# huskylens_servo.net
KiCad netlist of a schematic drawn in EAGLE
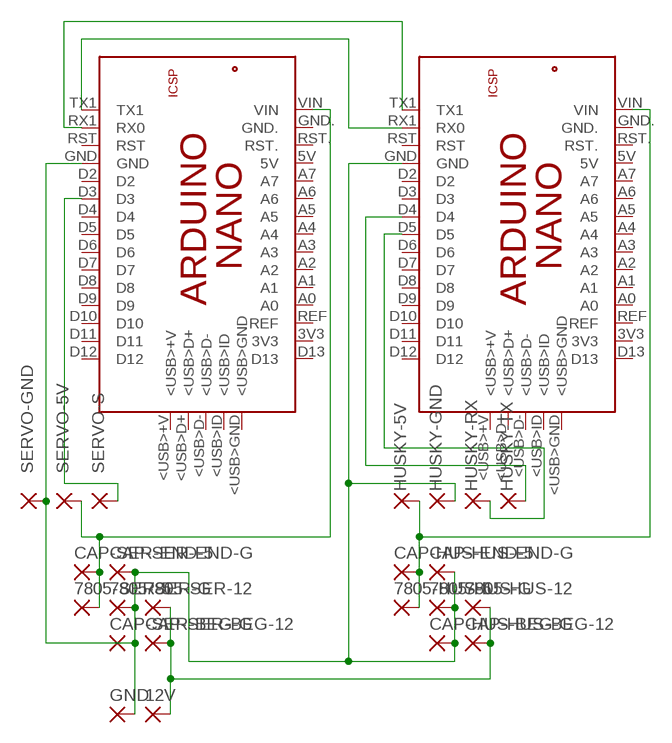
[diagram p0: schematic, sheet 1]

(export (version "E")
  (design (tool "Eeschema 10.0.6"))
  (components
    (comp (ref "12V")
      (value "2,15/1,0")
      (footprint "eagle-import:2,15_1,0")
      (libsource (lib "eagle-import") (part "2,15/1,0"))
    )
    (comp (ref "7805-HUS-5")
      (value "2,15/1,0")
      (footprint "eagle-import:2,15_1,0")
      (libsource (lib "eagle-import") (part "2,15/1,0"))
    )
    (comp (ref "7805-HUS-12")
      (value "2,15/1,0")
      (footprint "eagle-import:2,15_1,0")
      (libsource (lib "eagle-import") (part "2,15/1,0"))
    )
    (comp (ref "7805-HUS-G")
      (value "2,15/1,0")
      (footprint "eagle-import:2,15_1,0")
      (libsource (lib "eagle-import") (part "2,15/1,0"))
    )
    (comp (ref "7805-SER-5")
      (value "2,15/1,0")
      (footprint "eagle-import:2,15_1,0")
      (libsource (lib "eagle-import") (part "2,15/1,0"))
    )
    (comp (ref "7805-SER-12")
      (value "2,15/1,0")
      (footprint "eagle-import:2,15_1,0")
      (libsource (lib "eagle-import") (part "2,15/1,0"))
    )
    (comp (ref "7805-SER-G")
      (value "2,15/1,0")
      (footprint "eagle-import:2,15_1,0")
      (libsource (lib "eagle-import") (part "2,15/1,0"))
    )
    (comp (ref "CAP-HUS-BEG-12")
      (value "2,15/1,0")
      (footprint "eagle-import:2,15_1,0")
      (libsource (lib "eagle-import") (part "2,15/1,0"))
    )
    (comp (ref "CAP-HUS-BEG-G")
      (value "2,15/1,0")
      (footprint "eagle-import:2,15_1,0")
      (libsource (lib "eagle-import") (part "2,15/1,0"))
    )
    (comp (ref "CAP-HUS-END-5")
      (value "2,15/1,0")
      (footprint "eagle-import:2,15_1,0")
      (libsource (lib "eagle-import") (part "2,15/1,0"))
    )
    (comp (ref "CAP-HUS-END-G")
      (value "2,15/1,0")
      (footprint "eagle-import:2,15_1,0")
      (libsource (lib "eagle-import") (part "2,15/1,0"))
    )
    (comp (ref "CAP-SER-BEG-12")
      (value "2,15/1,0")
      (footprint "eagle-import:2,15_1,0")
      (libsource (lib "eagle-import") (part "2,15/1,0"))
    )
    (comp (ref "CAP-SER-BEG-G")
      (value "2,15/1,0")
      (footprint "eagle-import:2,15_1,0")
      (libsource (lib "eagle-import") (part "2,15/1,0"))
    )
    (comp (ref "CAP-SER-END-5")
      (value "2,15/1,0")
      (footprint "eagle-import:2,15_1,0")
      (libsource (lib "eagle-import") (part "2,15/1,0"))
    )
    (comp (ref "CAP-SER-END-G")
      (value "2,15/1,0")
      (footprint "eagle-import:2,15_1,0")
      (libsource (lib "eagle-import") (part "2,15/1,0"))
    )
    (comp (ref "GND")
      (value "2,15/1,0")
      (footprint "eagle-import:2,15_1,0")
      (libsource (lib "eagle-import") (part "2,15/1,0"))
    )
    (comp (ref "HUSKY-5V")
      (value "2,15/1,0")
      (footprint "eagle-import:2,15_1,0")
      (libsource (lib "eagle-import") (part "2,15/1,0"))
    )
    (comp (ref "HUSKY-ARD")
      (value "ARDUINO_NANO")
      (footprint "eagle-import:ARDUINO_NANO")
      (libsource (lib "eagle-import") (part "ARDUINO_NANO"))
    )
    (comp (ref "HUSKY-GND")
      (value "2,15/1,0")
      (footprint "eagle-import:2,15_1,0")
      (libsource (lib "eagle-import") (part "2,15/1,0"))
    )
    (comp (ref "HUSKY-RX")
      (value "2,15/1,0")
      (footprint "eagle-import:2,15_1,0")
      (libsource (lib "eagle-import") (part "2,15/1,0"))
    )
    (comp (ref "HUSKY-TX")
      (value "2,15/1,0")
      (footprint "eagle-import:2,15_1,0")
      (libsource (lib "eagle-import") (part "2,15/1,0"))
    )
    (comp (ref "SERVO-5V")
      (value "2,15/1,0")
      (footprint "eagle-import:2,15_1,0")
      (libsource (lib "eagle-import") (part "2,15/1,0"))
    )
    (comp (ref "SERVO-ARD")
      (value "ARDUINO_NANO")
      (footprint "eagle-import:ARDUINO_NANO")
      (libsource (lib "eagle-import") (part "ARDUINO_NANO"))
    )
    (comp (ref "SERVO-GND")
      (value "2,15/1,0")
      (footprint "eagle-import:2,15_1,0")
      (libsource (lib "eagle-import") (part "2,15/1,0"))
    )
    (comp (ref "SERVO-S")
      (value "2,15/1,0")
      (footprint "eagle-import:2,15_1,0")
      (libsource (lib "eagle-import") (part "2,15/1,0"))
    )
  )
  (nets
    (net (code "1") (name "Net-(12V-P)") (class "Default")
      (node (ref "12V") (pin "1") (pinfunction "P_1") (pintype "passive"))
      (node (ref "7805-HUS-12") (pin "1") (pinfunction "P_1") (pintype "passive"))
      (node (ref "7805-SER-12") (pin "1") (pinfunction "P_1") (pintype "passive"))
      (node (ref "CAP-HUS-BEG-12") (pin "1") (pinfunction "P_1") (pintype "passive"))
      (node (ref "CAP-SER-BEG-12") (pin "1") (pinfunction "P_1") (pintype "passive"))
    )
    (net (code "2") (name "Net-(7805-HUS-5-P)") (class "Default")
      (node (ref "7805-HUS-5") (pin "1") (pinfunction "P_1") (pintype "passive"))
      (node (ref "CAP-HUS-END-5") (pin "1") (pinfunction "P_1") (pintype "passive"))
      (node (ref "HUSKY-5V") (pin "1") (pinfunction "P_1") (pintype "passive"))
      (node (ref "HUSKY-ARD") (pin "VIN") (pinfunction "VIN_VIN") (pintype "bidirectional"))
    )
    (net (code "3") (name "Net-(7805-HUS-G-P)") (class "Default")
      (node (ref "7805-HUS-G") (pin "1") (pinfunction "P_1") (pintype "passive"))
      (node (ref "7805-SER-G") (pin "1") (pinfunction "P_1") (pintype "passive"))
      (node (ref "CAP-HUS-BEG-G") (pin "1") (pinfunction "P_1") (pintype "passive"))
      (node (ref "CAP-HUS-END-G") (pin "1") (pinfunction "P_1") (pintype "passive"))
      (node (ref "CAP-SER-BEG-G") (pin "1") (pinfunction "P_1") (pintype "passive"))
      (node (ref "CAP-SER-END-G") (pin "1") (pinfunction "P_1") (pintype "passive"))
      (node (ref "GND") (pin "1") (pinfunction "P_1") (pintype "passive"))
      (node (ref "HUSKY-ARD") (pin "GND") (pinfunction "GND_GND") (pintype "bidirectional"))
      (node (ref "HUSKY-GND") (pin "1") (pinfunction "P_1") (pintype "passive"))
      (node (ref "SERVO-ARD") (pin "GND") (pinfunction "GND_GND") (pintype "bidirectional"))
      (node (ref "SERVO-GND") (pin "1") (pinfunction "P_1") (pintype "passive"))
    )
    (net (code "4") (name "Net-(7805-SER-5-P)") (class "Default")
      (node (ref "7805-SER-5") (pin "1") (pinfunction "P_1") (pintype "passive"))
      (node (ref "CAP-SER-END-5") (pin "1") (pinfunction "P_1") (pintype "passive"))
      (node (ref "SERVO-5V") (pin "1") (pinfunction "P_1") (pintype "passive"))
      (node (ref "SERVO-ARD") (pin "VIN") (pinfunction "VIN_VIN") (pintype "bidirectional"))
    )
    (net (code "5") (name "Net-(HUSKY-ARD-RX0)") (class "Default")
      (node (ref "HUSKY-ARD") (pin "RX1") (pinfunction "RX0_RX1") (pintype "bidirectional"))
      (node (ref "SERVO-ARD") (pin "TX1") (pinfunction "TX1_TX1") (pintype "bidirectional"))
    )
    (net (code "6") (name "Net-(HUSKY-RX-P)") (class "Default")
      (node (ref "HUSKY-ARD") (pin "D5") (pinfunction "D5_D5") (pintype "bidirectional"))
      (node (ref "HUSKY-RX") (pin "1") (pinfunction "P_1") (pintype "passive"))
    )
    (net (code "7") (name "Net-(HUSKY-TX-P)") (class "Default")
      (node (ref "HUSKY-ARD") (pin "D4") (pinfunction "D4_D4") (pintype "bidirectional"))
      (node (ref "HUSKY-TX") (pin "1") (pinfunction "P_1") (pintype "passive"))
    )
    (net (code "8") (name "Net-(SERVO-ARD-RX0)") (class "Default")
      (node (ref "HUSKY-ARD") (pin "TX1") (pinfunction "TX1_TX1") (pintype "bidirectional"))
      (node (ref "SERVO-ARD") (pin "RX1") (pinfunction "RX0_RX1") (pintype "bidirectional"))
    )
    (net (code "9") (name "Net-(SERVO-S-P)") (class "Default")
      (node (ref "SERVO-ARD") (pin "D3") (pinfunction "D3_D3") (pintype "bidirectional"))
      (node (ref "SERVO-S") (pin "1") (pinfunction "P_1") (pintype "passive"))
    )
    (net (code "10") (name "unconnected-(HUSKY-ARD-Pad3V3)") (class "Default")
      (node (ref "HUSKY-ARD") (pin "3V3") (pinfunction "3V3_3V3") (pintype "bidirectional"))
    )
    (net (code "11") (name "unconnected-(HUSKY-ARD-Pad5V)") (class "Default")
      (node (ref "HUSKY-ARD") (pin "5V") (pinfunction "5V_5V") (pintype "bidirectional"))
    )
    (net (code "12") (name "unconnected-(HUSKY-ARD-Pad5V.)") (class "Default")
      (node (ref "HUSKY-ARD") (pin "5V.") (pinfunction "5V._5V.") (pintype "bidirectional"))
    )
    (net (code "13") (name "unconnected-(HUSKY-ARD-Pad<USB>+V)") (class "Default")
      (node (ref "HUSKY-ARD") (pin "<USB>+V") (pinfunction "<USB>+V_<USB>+V") (pintype "bidirectional"))
    )
    (net (code "14") (name "unconnected-(HUSKY-ARD-Pad<USB>D+)") (class "Default")
      (node (ref "HUSKY-ARD") (pin "<USB>D+") (pinfunction "<USB>D+_<USB>D+") (pintype "bidirectional"))
    )
    (net (code "15") (name "unconnected-(HUSKY-ARD-Pad<USB>D-)") (class "Default")
      (node (ref "HUSKY-ARD") (pin "<USB>D-") (pinfunction "<USB>D-_<USB>D-") (pintype "bidirectional"))
    )
    (net (code "16") (name "unconnected-(HUSKY-ARD-Pad<USB>GND)") (class "Default")
      (node (ref "HUSKY-ARD") (pin "<USB>GND") (pinfunction "<USB>GND_<USB>GND") (pintype "bidirectional"))
    )
    (net (code "17") (name "unconnected-(HUSKY-ARD-Pad<USB>ID)") (class "Default")
      (node (ref "HUSKY-ARD") (pin "<USB>ID") (pinfunction "<USB>ID_<USB>ID") (pintype "bidirectional"))
    )
    (net (code "18") (name "unconnected-(HUSKY-ARD-PadA0)") (class "Default")
      (node (ref "HUSKY-ARD") (pin "A0") (pinfunction "A0_A0") (pintype "bidirectional"))
    )
    (net (code "19") (name "unconnected-(HUSKY-ARD-PadA1)") (class "Default")
      (node (ref "HUSKY-ARD") (pin "A1") (pinfunction "A1_A1") (pintype "bidirectional"))
    )
    (net (code "20") (name "unconnected-(HUSKY-ARD-PadA2)") (class "Default")
      (node (ref "HUSKY-ARD") (pin "A2") (pinfunction "A2_A2") (pintype "bidirectional"))
    )
    (net (code "21") (name "unconnected-(HUSKY-ARD-PadA3)") (class "Default")
      (node (ref "HUSKY-ARD") (pin "A3") (pinfunction "A3_A3") (pintype "bidirectional"))
    )
    (net (code "22") (name "unconnected-(HUSKY-ARD-PadA4)") (class "Default")
      (node (ref "HUSKY-ARD") (pin "A4") (pinfunction "A4_A4") (pintype "bidirectional"))
    )
    (net (code "23") (name "unconnected-(HUSKY-ARD-PadA5)") (class "Default")
      (node (ref "HUSKY-ARD") (pin "A5") (pinfunction "A5_A5") (pintype "bidirectional"))
    )
    (net (code "24") (name "unconnected-(HUSKY-ARD-PadA6)") (class "Default")
      (node (ref "HUSKY-ARD") (pin "A6") (pinfunction "A6_A6") (pintype "bidirectional"))
    )
    (net (code "25") (name "unconnected-(HUSKY-ARD-PadA7)") (class "Default")
      (node (ref "HUSKY-ARD") (pin "A7") (pinfunction "A7_A7") (pintype "bidirectional"))
    )
    (net (code "26") (name "unconnected-(HUSKY-ARD-PadD2)") (class "Default")
      (node (ref "HUSKY-ARD") (pin "D2") (pinfunction "D2_D2") (pintype "bidirectional"))
    )
    (net (code "27") (name "unconnected-(HUSKY-ARD-PadD3)") (class "Default")
      (node (ref "HUSKY-ARD") (pin "D3") (pinfunction "D3_D3") (pintype "bidirectional"))
    )
    (net (code "28") (name "unconnected-(HUSKY-ARD-PadD6)") (class "Default")
      (node (ref "HUSKY-ARD") (pin "D6") (pinfunction "D6_D6") (pintype "bidirectional"))
    )
    (net (code "29") (name "unconnected-(HUSKY-ARD-PadD7)") (class "Default")
      (node (ref "HUSKY-ARD") (pin "D7") (pinfunction "D7_D7") (pintype "bidirectional"))
    )
    (net (code "30") (name "unconnected-(HUSKY-ARD-PadD8)") (class "Default")
      (node (ref "HUSKY-ARD") (pin "D8") (pinfunction "D8_D8") (pintype "bidirectional"))
    )
    (net (code "31") (name "unconnected-(HUSKY-ARD-PadD9)") (class "Default")
      (node (ref "HUSKY-ARD") (pin "D9") (pinfunction "D9_D9") (pintype "bidirectional"))
    )
    (net (code "32") (name "unconnected-(HUSKY-ARD-PadD10)") (class "Default")
      (node (ref "HUSKY-ARD") (pin "D10") (pinfunction "D10_D10") (pintype "bidirectional"))
    )
    (net (code "33") (name "unconnected-(HUSKY-ARD-PadD11)") (class "Default")
      (node (ref "HUSKY-ARD") (pin "D11") (pinfunction "D11_D11") (pintype "bidirectional"))
    )
    (net (code "34") (name "unconnected-(HUSKY-ARD-PadD12)") (class "Default")
      (node (ref "HUSKY-ARD") (pin "D12") (pinfunction "D12_D12") (pintype "bidirectional"))
    )
    (net (code "35") (name "unconnected-(HUSKY-ARD-PadD13)") (class "Default")
      (node (ref "HUSKY-ARD") (pin "D13") (pinfunction "D13_D13") (pintype "bidirectional"))
    )
    (net (code "36") (name "unconnected-(HUSKY-ARD-PadGND.)") (class "Default")
      (node (ref "HUSKY-ARD") (pin "GND.") (pinfunction "GND._GND.") (pintype "bidirectional"))
    )
    (net (code "37") (name "unconnected-(HUSKY-ARD-PadGND_)") (class "Default")
      (node (ref "HUSKY-ARD") (pin "GND_") (pinfunction "GND__GND_") (pintype "bidirectional"))
    )
    (net (code "38") (name "unconnected-(HUSKY-ARD-PadMISO)") (class "Default")
      (node (ref "HUSKY-ARD") (pin "MISO") (pinfunction "MISO_MISO") (pintype "bidirectional"))
    )
    (net (code "39") (name "unconnected-(HUSKY-ARD-PadMOSI)") (class "Default")
      (node (ref "HUSKY-ARD") (pin "MOSI") (pinfunction "MOSI_MOSI") (pintype "bidirectional"))
    )
    (net (code "40") (name "unconnected-(HUSKY-ARD-PadREF)") (class "Default")
      (node (ref "HUSKY-ARD") (pin "REF") (pinfunction "REF_REF") (pintype "bidirectional"))
    )
    (net (code "41") (name "unconnected-(HUSKY-ARD-PadRESET..)") (class "Default")
      (node (ref "HUSKY-ARD") (pin "RESET..") (pinfunction "RESET.._RESET..") (pintype "bidirectional"))
    )
    (net (code "42") (name "unconnected-(HUSKY-ARD-PadRST)") (class "Default")
      (node (ref "HUSKY-ARD") (pin "RST") (pinfunction "RST_RST") (pintype "bidirectional"))
    )
    (net (code "43") (name "unconnected-(HUSKY-ARD-PadRST.)") (class "Default")
      (node (ref "HUSKY-ARD") (pin "RST.") (pinfunction "RST._RST.") (pintype "bidirectional"))
    )
    (net (code "44") (name "unconnected-(HUSKY-ARD-PadSCK)") (class "Default")
      (node (ref "HUSKY-ARD") (pin "SCK") (pinfunction "SCK_SCK") (pintype "bidirectional"))
    )
    (net (code "45") (name "unconnected-(SERVO-ARD-Pad3V3)") (class "Default")
      (node (ref "SERVO-ARD") (pin "3V3") (pinfunction "3V3_3V3") (pintype "bidirectional"))
    )
    (net (code "46") (name "unconnected-(SERVO-ARD-Pad5V)") (class "Default")
      (node (ref "SERVO-ARD") (pin "5V") (pinfunction "5V_5V") (pintype "bidirectional"))
    )
    (net (code "47") (name "unconnected-(SERVO-ARD-Pad5V.)") (class "Default")
      (node (ref "SERVO-ARD") (pin "5V.") (pinfunction "5V._5V.") (pintype "bidirectional"))
    )
    (net (code "48") (name "unconnected-(SERVO-ARD-Pad<USB>+V)") (class "Default")
      (node (ref "SERVO-ARD") (pin "<USB>+V") (pinfunction "<USB>+V_<USB>+V") (pintype "bidirectional"))
    )
    (net (code "49") (name "unconnected-(SERVO-ARD-Pad<USB>D+)") (class "Default")
      (node (ref "SERVO-ARD") (pin "<USB>D+") (pinfunction "<USB>D+_<USB>D+") (pintype "bidirectional"))
    )
    (net (code "50") (name "unconnected-(SERVO-ARD-Pad<USB>D-)") (class "Default")
      (node (ref "SERVO-ARD") (pin "<USB>D-") (pinfunction "<USB>D-_<USB>D-") (pintype "bidirectional"))
    )
    (net (code "51") (name "unconnected-(SERVO-ARD-Pad<USB>GND)") (class "Default")
      (node (ref "SERVO-ARD") (pin "<USB>GND") (pinfunction "<USB>GND_<USB>GND") (pintype "bidirectional"))
    )
    (net (code "52") (name "unconnected-(SERVO-ARD-Pad<USB>ID)") (class "Default")
      (node (ref "SERVO-ARD") (pin "<USB>ID") (pinfunction "<USB>ID_<USB>ID") (pintype "bidirectional"))
    )
    (net (code "53") (name "unconnected-(SERVO-ARD-PadA0)") (class "Default")
      (node (ref "SERVO-ARD") (pin "A0") (pinfunction "A0_A0") (pintype "bidirectional"))
    )
    (net (code "54") (name "unconnected-(SERVO-ARD-PadA1)") (class "Default")
      (node (ref "SERVO-ARD") (pin "A1") (pinfunction "A1_A1") (pintype "bidirectional"))
    )
    (net (code "55") (name "unconnected-(SERVO-ARD-PadA2)") (class "Default")
      (node (ref "SERVO-ARD") (pin "A2") (pinfunction "A2_A2") (pintype "bidirectional"))
    )
    (net (code "56") (name "unconnected-(SERVO-ARD-PadA3)") (class "Default")
      (node (ref "SERVO-ARD") (pin "A3") (pinfunction "A3_A3") (pintype "bidirectional"))
    )
    (net (code "57") (name "unconnected-(SERVO-ARD-PadA4)") (class "Default")
      (node (ref "SERVO-ARD") (pin "A4") (pinfunction "A4_A4") (pintype "bidirectional"))
    )
    (net (code "58") (name "unconnected-(SERVO-ARD-PadA5)") (class "Default")
      (node (ref "SERVO-ARD") (pin "A5") (pinfunction "A5_A5") (pintype "bidirectional"))
    )
    (net (code "59") (name "unconnected-(SERVO-ARD-PadA6)") (class "Default")
      (node (ref "SERVO-ARD") (pin "A6") (pinfunction "A6_A6") (pintype "bidirectional"))
    )
    (net (code "60") (name "unconnected-(SERVO-ARD-PadA7)") (class "Default")
      (node (ref "SERVO-ARD") (pin "A7") (pinfunction "A7_A7") (pintype "bidirectional"))
    )
    (net (code "61") (name "unconnected-(SERVO-ARD-PadD2)") (class "Default")
      (node (ref "SERVO-ARD") (pin "D2") (pinfunction "D2_D2") (pintype "bidirectional"))
    )
    (net (code "62") (name "unconnected-(SERVO-ARD-PadD4)") (class "Default")
      (node (ref "SERVO-ARD") (pin "D4") (pinfunction "D4_D4") (pintype "bidirectional"))
    )
    (net (code "63") (name "unconnected-(SERVO-ARD-PadD5)") (class "Default")
      (node (ref "SERVO-ARD") (pin "D5") (pinfunction "D5_D5") (pintype "bidirectional"))
    )
    (net (code "64") (name "unconnected-(SERVO-ARD-PadD6)") (class "Default")
      (node (ref "SERVO-ARD") (pin "D6") (pinfunction "D6_D6") (pintype "bidirectional"))
    )
    (net (code "65") (name "unconnected-(SERVO-ARD-PadD7)") (class "Default")
      (node (ref "SERVO-ARD") (pin "D7") (pinfunction "D7_D7") (pintype "bidirectional"))
    )
    (net (code "66") (name "unconnected-(SERVO-ARD-PadD8)") (class "Default")
      (node (ref "SERVO-ARD") (pin "D8") (pinfunction "D8_D8") (pintype "bidirectional"))
    )
    (net (code "67") (name "unconnected-(SERVO-ARD-PadD9)") (class "Default")
      (node (ref "SERVO-ARD") (pin "D9") (pinfunction "D9_D9") (pintype "bidirectional"))
    )
    (net (code "68") (name "unconnected-(SERVO-ARD-PadD10)") (class "Default")
      (node (ref "SERVO-ARD") (pin "D10") (pinfunction "D10_D10") (pintype "bidirectional"))
    )
    (net (code "69") (name "unconnected-(SERVO-ARD-PadD11)") (class "Default")
      (node (ref "SERVO-ARD") (pin "D11") (pinfunction "D11_D11") (pintype "bidirectional"))
    )
    (net (code "70") (name "unconnected-(SERVO-ARD-PadD12)") (class "Default")
      (node (ref "SERVO-ARD") (pin "D12") (pinfunction "D12_D12") (pintype "bidirectional"))
    )
    (net (code "71") (name "unconnected-(SERVO-ARD-PadD13)") (class "Default")
      (node (ref "SERVO-ARD") (pin "D13") (pinfunction "D13_D13") (pintype "bidirectional"))
    )
    (net (code "72") (name "unconnected-(SERVO-ARD-PadGND.)") (class "Default")
      (node (ref "SERVO-ARD") (pin "GND.") (pinfunction "GND._GND.") (pintype "bidirectional"))
    )
    (net (code "73") (name "unconnected-(SERVO-ARD-PadGND_)") (class "Default")
      (node (ref "SERVO-ARD") (pin "GND_") (pinfunction "GND__GND_") (pintype "bidirectional"))
    )
    (net (code "74") (name "unconnected-(SERVO-ARD-PadMISO)") (class "Default")
      (node (ref "SERVO-ARD") (pin "MISO") (pinfunction "MISO_MISO") (pintype "bidirectional"))
    )
    (net (code "75") (name "unconnected-(SERVO-ARD-PadMOSI)") (class "Default")
      (node (ref "SERVO-ARD") (pin "MOSI") (pinfunction "MOSI_MOSI") (pintype "bidirectional"))
    )
    (net (code "76") (name "unconnected-(SERVO-ARD-PadREF)") (class "Default")
      (node (ref "SERVO-ARD") (pin "REF") (pinfunction "REF_REF") (pintype "bidirectional"))
    )
    (net (code "77") (name "unconnected-(SERVO-ARD-PadRESET..)") (class "Default")
      (node (ref "SERVO-ARD") (pin "RESET..") (pinfunction "RESET.._RESET..") (pintype "bidirectional"))
    )
    (net (code "78") (name "unconnected-(SERVO-ARD-PadRST)") (class "Default")
      (node (ref "SERVO-ARD") (pin "RST") (pinfunction "RST_RST") (pintype "bidirectional"))
    )
    (net (code "79") (name "unconnected-(SERVO-ARD-PadRST.)") (class "Default")
      (node (ref "SERVO-ARD") (pin "RST.") (pinfunction "RST._RST.") (pintype "bidirectional"))
    )
    (net (code "80") (name "unconnected-(SERVO-ARD-PadSCK)") (class "Default")
      (node (ref "SERVO-ARD") (pin "SCK") (pinfunction "SCK_SCK") (pintype "bidirectional"))
    )
  )
)
